# SCH_vdk.net
KiCad netlist of a schematic drawn in EasyEDA
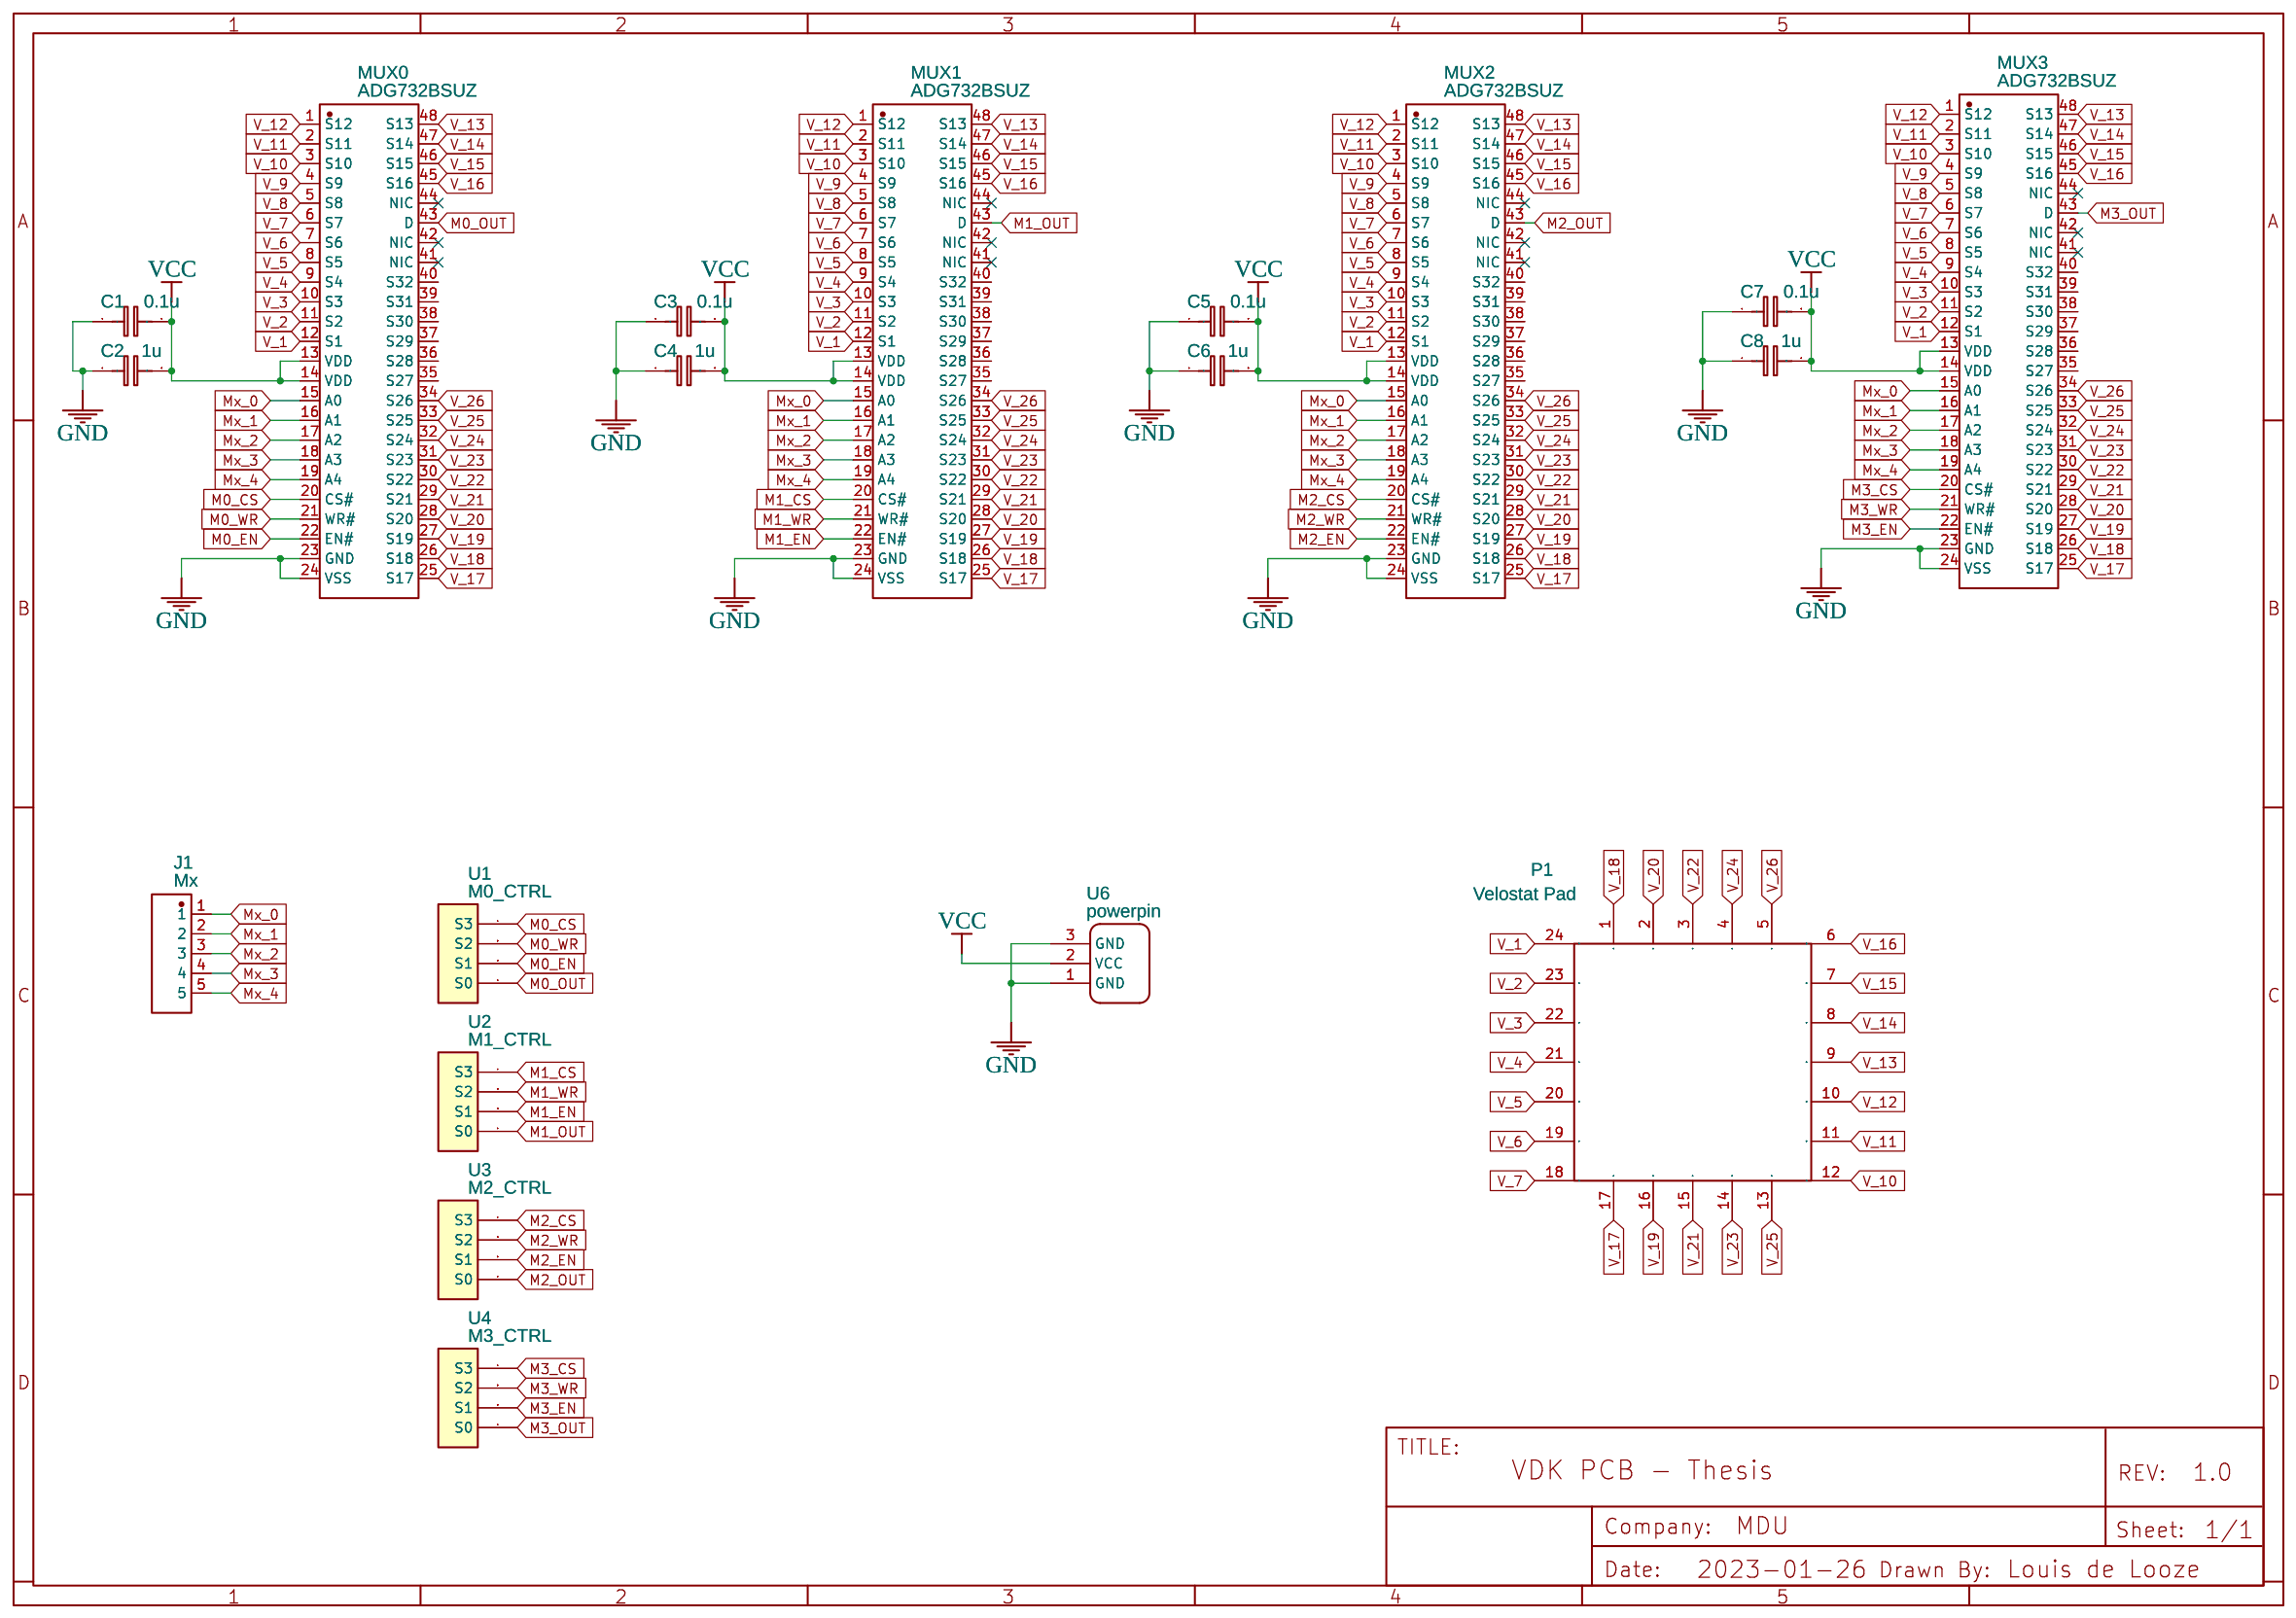
[diagram p0: schematic sheet]

(export (version "E")
  (design (tool "Eeschema 10.0.6"))
  (components
    (comp (ref "C1") (value "0.1u") (libsource (lib "") (part "Cap_0805_EU")))
    (comp (ref "C2") (value "1u") (libsource (lib "") (part "Cap_0805_EU")))
    (comp (ref "C3") (value "0.1u") (libsource (lib "") (part "Cap_0805_EU_1")))
    (comp (ref "C4") (value "1u") (libsource (lib "") (part "Cap_0805_EU_1")))
    (comp (ref "C5") (value "0.1u") (libsource (lib "") (part "Cap_0805_EU")))
    (comp (ref "C6") (value "1u") (libsource (lib "") (part "Cap_0805_EU")))
    (comp (ref "C7") (value "0.1u") (libsource (lib "") (part "Cap_0805_EU")))
    (comp (ref "C8") (value "1u") (libsource (lib "") (part "Cap_0805_EU")))
    (comp (ref "J1") (value "Mx") (libsource (lib "") (part "5-pin")))
    (comp (ref "MUX0")
      (value "ADG732BSUZ")
      (fields (field (name "BOM_Supplier Part") "C579103"))
      (libsource (lib "") (part "ADG732BSUZ"))
    )
    (comp (ref "MUX1")
      (value "ADG732BSUZ")
      (fields (field (name "BOM_Supplier Part") "C579103"))
      (libsource (lib "") (part "ADG732BSUZ"))
    )
    (comp (ref "MUX2")
      (value "ADG732BSUZ")
      (fields (field (name "BOM_Supplier Part") "C579103"))
      (libsource (lib "") (part "ADG732BSUZ"))
    )
    (comp (ref "MUX3")
      (value "ADG732BSUZ")
      (fields (field (name "BOM_Supplier Part") "C579103"))
      (libsource (lib "") (part "ADG732BSUZ"))
    )
    (comp (ref "P1") (value "Velostat Pad") (libsource (lib "") (part "Velostat Pad")))
    (comp (ref "U1")
      (value "M0_CTRL")
      (fields (field (name "BOM_Manufacturer Part") "New SchematicLib"))
      (libsource (lib "") (part "4 pin 16ch mux control"))
    )
    (comp (ref "U2")
      (value "M1_CTRL")
      (fields (field (name "BOM_Manufacturer Part") "New SchematicLib"))
      (libsource (lib "") (part "4 pin 16ch mux control"))
    )
    (comp (ref "U3")
      (value "M2_CTRL")
      (fields (field (name "BOM_Manufacturer Part") "New SchematicLib"))
      (libsource (lib "") (part "4 pin 16ch mux control"))
    )
    (comp (ref "U4")
      (value "M3_CTRL")
      (fields (field (name "BOM_Manufacturer Part") "New SchematicLib"))
      (libsource (lib "") (part "4 pin 16ch mux control"))
    )
    (comp (ref "U6") (value "powerpin") (libsource (lib "") (part "servo-header-3pin")))
  )
  (nets
    (net (code "1") (name "GND") (class "Default")
      (node (ref "C1") (pin "1") (pinfunction "1_1") (pintype "unspecified"))
      (node (ref "C2") (pin "1") (pinfunction "1_1") (pintype "unspecified"))
      (node (ref "C3") (pin "1") (pinfunction "1_1") (pintype "unspecified"))
      (node (ref "C4") (pin "1") (pinfunction "1_1") (pintype "unspecified"))
      (node (ref "C5") (pin "1") (pinfunction "1_1") (pintype "unspecified"))
      (node (ref "C6") (pin "1") (pinfunction "1_1") (pintype "unspecified"))
      (node (ref "C7") (pin "1") (pinfunction "1_1") (pintype "unspecified"))
      (node (ref "C8") (pin "1") (pinfunction "1_1") (pintype "unspecified"))
      (node (ref "MUX0") (pin "23") (pinfunction "GND_23") (pintype "unspecified"))
      (node (ref "MUX0") (pin "24") (pinfunction "VSS_24") (pintype "unspecified"))
      (node (ref "MUX1") (pin "23") (pinfunction "GND_23") (pintype "unspecified"))
      (node (ref "MUX1") (pin "24") (pinfunction "VSS_24") (pintype "unspecified"))
      (node (ref "MUX2") (pin "23") (pinfunction "GND_23") (pintype "unspecified"))
      (node (ref "MUX2") (pin "24") (pinfunction "VSS_24") (pintype "unspecified"))
      (node (ref "MUX3") (pin "23") (pinfunction "GND_23") (pintype "unspecified"))
      (node (ref "MUX3") (pin "24") (pinfunction "VSS_24") (pintype "unspecified"))
      (node (ref "U6") (pin "1") (pinfunction "GND_1") (pintype "unspecified"))
      (node (ref "U6") (pin "3") (pinfunction "GND_3") (pintype "unspecified"))
    )
    (net (code "2") (name "M0_CS") (class "Default")
      (node (ref "MUX0") (pin "20") (pinfunction "CS#_20") (pintype "unspecified"))
      (node (ref "U1") (pin "4") (pinfunction "S3_4") (pintype "input"))
    )
    (net (code "3") (name "M0_EN") (class "Default")
      (node (ref "MUX0") (pin "22") (pinfunction "EN#_22") (pintype "unspecified"))
      (node (ref "U1") (pin "2") (pinfunction "S1_2") (pintype "input"))
    )
    (net (code "4") (name "M0_OUT") (class "Default")
      (node (ref "MUX0") (pin "43") (pinfunction "D_43") (pintype "unspecified"))
      (node (ref "U1") (pin "1") (pinfunction "S0_1") (pintype "input"))
    )
    (net (code "5") (name "M0_WR") (class "Default")
      (node (ref "MUX0") (pin "21") (pinfunction "WR#_21") (pintype "unspecified"))
      (node (ref "U1") (pin "3") (pinfunction "S2_3") (pintype "input"))
    )
    (net (code "6") (name "M1_CS") (class "Default")
      (node (ref "MUX1") (pin "20") (pinfunction "CS#_20") (pintype "unspecified"))
      (node (ref "U2") (pin "4") (pinfunction "S3_4") (pintype "input"))
    )
    (net (code "7") (name "M1_EN") (class "Default")
      (node (ref "MUX1") (pin "22") (pinfunction "EN#_22") (pintype "unspecified"))
      (node (ref "U2") (pin "2") (pinfunction "S1_2") (pintype "input"))
    )
    (net (code "8") (name "M1_OUT") (class "Default")
      (node (ref "MUX1") (pin "43") (pinfunction "D_43") (pintype "unspecified"))
      (node (ref "U2") (pin "1") (pinfunction "S0_1") (pintype "input"))
    )
    (net (code "9") (name "M1_WR") (class "Default")
      (node (ref "MUX1") (pin "21") (pinfunction "WR#_21") (pintype "unspecified"))
      (node (ref "U2") (pin "3") (pinfunction "S2_3") (pintype "input"))
    )
    (net (code "10") (name "M2_CS") (class "Default")
      (node (ref "MUX2") (pin "20") (pinfunction "CS#_20") (pintype "unspecified"))
      (node (ref "U3") (pin "4") (pinfunction "S3_4") (pintype "input"))
    )
    (net (code "11") (name "M2_EN") (class "Default")
      (node (ref "MUX2") (pin "22") (pinfunction "EN#_22") (pintype "unspecified"))
      (node (ref "U3") (pin "2") (pinfunction "S1_2") (pintype "input"))
    )
    (net (code "12") (name "M2_OUT") (class "Default")
      (node (ref "MUX2") (pin "43") (pinfunction "D_43") (pintype "unspecified"))
      (node (ref "U3") (pin "1") (pinfunction "S0_1") (pintype "input"))
    )
    (net (code "13") (name "M2_WR") (class "Default")
      (node (ref "MUX2") (pin "21") (pinfunction "WR#_21") (pintype "unspecified"))
      (node (ref "U3") (pin "3") (pinfunction "S2_3") (pintype "input"))
    )
    (net (code "14") (name "M3_CS") (class "Default")
      (node (ref "MUX3") (pin "20") (pinfunction "CS#_20") (pintype "unspecified"))
      (node (ref "U4") (pin "4") (pinfunction "S3_4") (pintype "input"))
    )
    (net (code "15") (name "M3_EN") (class "Default")
      (node (ref "MUX3") (pin "22") (pinfunction "EN#_22") (pintype "unspecified"))
      (node (ref "U4") (pin "2") (pinfunction "S1_2") (pintype "input"))
    )
    (net (code "16") (name "M3_OUT") (class "Default")
      (node (ref "MUX3") (pin "43") (pinfunction "D_43") (pintype "unspecified"))
      (node (ref "U4") (pin "1") (pinfunction "S0_1") (pintype "input"))
    )
    (net (code "17") (name "M3_WR") (class "Default")
      (node (ref "MUX3") (pin "21") (pinfunction "WR#_21") (pintype "unspecified"))
      (node (ref "U4") (pin "3") (pinfunction "S2_3") (pintype "input"))
    )
    (net (code "18") (name "Mx_0") (class "Default")
      (node (ref "J1") (pin "1") (pinfunction "1_1") (pintype "unspecified"))
      (node (ref "MUX0") (pin "15") (pinfunction "A0_15") (pintype "unspecified"))
      (node (ref "MUX1") (pin "15") (pinfunction "A0_15") (pintype "unspecified"))
      (node (ref "MUX2") (pin "15") (pinfunction "A0_15") (pintype "unspecified"))
      (node (ref "MUX3") (pin "15") (pinfunction "A0_15") (pintype "unspecified"))
    )
    (net (code "19") (name "Mx_1") (class "Default")
      (node (ref "J1") (pin "2") (pinfunction "2_2") (pintype "unspecified"))
      (node (ref "MUX0") (pin "16") (pinfunction "A1_16") (pintype "unspecified"))
      (node (ref "MUX1") (pin "16") (pinfunction "A1_16") (pintype "unspecified"))
      (node (ref "MUX2") (pin "16") (pinfunction "A1_16") (pintype "unspecified"))
      (node (ref "MUX3") (pin "16") (pinfunction "A1_16") (pintype "unspecified"))
    )
    (net (code "20") (name "Mx_2") (class "Default")
      (node (ref "J1") (pin "3") (pinfunction "3_3") (pintype "unspecified"))
      (node (ref "MUX0") (pin "17") (pinfunction "A2_17") (pintype "unspecified"))
      (node (ref "MUX1") (pin "17") (pinfunction "A2_17") (pintype "unspecified"))
      (node (ref "MUX2") (pin "17") (pinfunction "A2_17") (pintype "unspecified"))
      (node (ref "MUX3") (pin "17") (pinfunction "A2_17") (pintype "unspecified"))
    )
    (net (code "21") (name "Mx_3") (class "Default")
      (node (ref "J1") (pin "4") (pinfunction "4_4") (pintype "unspecified"))
      (node (ref "MUX0") (pin "18") (pinfunction "A3_18") (pintype "unspecified"))
      (node (ref "MUX1") (pin "18") (pinfunction "A3_18") (pintype "unspecified"))
      (node (ref "MUX2") (pin "18") (pinfunction "A3_18") (pintype "unspecified"))
      (node (ref "MUX3") (pin "18") (pinfunction "A3_18") (pintype "unspecified"))
    )
    (net (code "22") (name "Mx_4") (class "Default")
      (node (ref "J1") (pin "5") (pinfunction "5_5") (pintype "unspecified"))
      (node (ref "MUX0") (pin "19") (pinfunction "A4_19") (pintype "unspecified"))
      (node (ref "MUX1") (pin "19") (pinfunction "A4_19") (pintype "unspecified"))
      (node (ref "MUX2") (pin "19") (pinfunction "A4_19") (pintype "unspecified"))
      (node (ref "MUX3") (pin "19") (pinfunction "A4_19") (pintype "unspecified"))
    )
    (net (code "23") (name "VCC") (class "Default")
      (node (ref "C1") (pin "2") (pinfunction "2_2") (pintype "unspecified"))
      (node (ref "C2") (pin "2") (pinfunction "2_2") (pintype "unspecified"))
      (node (ref "C3") (pin "2") (pinfunction "2_2") (pintype "unspecified"))
      (node (ref "C4") (pin "2") (pinfunction "2_2") (pintype "unspecified"))
      (node (ref "C5") (pin "2") (pinfunction "2_2") (pintype "unspecified"))
      (node (ref "C6") (pin "2") (pinfunction "2_2") (pintype "unspecified"))
      (node (ref "C7") (pin "2") (pinfunction "2_2") (pintype "unspecified"))
      (node (ref "C8") (pin "2") (pinfunction "2_2") (pintype "unspecified"))
      (node (ref "MUX0") (pin "13") (pinfunction "VDD_13") (pintype "unspecified"))
      (node (ref "MUX0") (pin "14") (pinfunction "VDD_14") (pintype "unspecified"))
      (node (ref "MUX1") (pin "13") (pinfunction "VDD_13") (pintype "unspecified"))
      (node (ref "MUX1") (pin "14") (pinfunction "VDD_14") (pintype "unspecified"))
      (node (ref "MUX2") (pin "13") (pinfunction "VDD_13") (pintype "unspecified"))
      (node (ref "MUX2") (pin "14") (pinfunction "VDD_14") (pintype "unspecified"))
      (node (ref "MUX3") (pin "13") (pinfunction "VDD_13") (pintype "unspecified"))
      (node (ref "MUX3") (pin "14") (pinfunction "VDD_14") (pintype "unspecified"))
      (node (ref "U6") (pin "2") (pinfunction "VCC_2") (pintype "unspecified"))
    )
    (net (code "24") (name "V_1") (class "Default")
      (node (ref "MUX0") (pin "12") (pinfunction "S1_12") (pintype "unspecified"))
      (node (ref "MUX1") (pin "12") (pinfunction "S1_12") (pintype "unspecified"))
      (node (ref "MUX2") (pin "12") (pinfunction "S1_12") (pintype "unspecified"))
      (node (ref "MUX3") (pin "12") (pinfunction "S1_12") (pintype "unspecified"))
      (node (ref "P1") (pin "24") (pinfunction "1_24") (pintype "unspecified"))
    )
    (net (code "25") (name "V_2") (class "Default")
      (node (ref "MUX0") (pin "11") (pinfunction "S2_11") (pintype "unspecified"))
      (node (ref "MUX1") (pin "11") (pinfunction "S2_11") (pintype "unspecified"))
      (node (ref "MUX2") (pin "11") (pinfunction "S2_11") (pintype "unspecified"))
      (node (ref "MUX3") (pin "11") (pinfunction "S2_11") (pintype "unspecified"))
      (node (ref "P1") (pin "23") (pinfunction "1_23") (pintype "unspecified"))
    )
    (net (code "26") (name "V_3") (class "Default")
      (node (ref "MUX0") (pin "10") (pinfunction "S3_10") (pintype "unspecified"))
      (node (ref "MUX1") (pin "10") (pinfunction "S3_10") (pintype "unspecified"))
      (node (ref "MUX2") (pin "10") (pinfunction "S3_10") (pintype "unspecified"))
      (node (ref "MUX3") (pin "10") (pinfunction "S3_10") (pintype "unspecified"))
      (node (ref "P1") (pin "22") (pinfunction "1_22") (pintype "unspecified"))
    )
    (net (code "27") (name "V_4") (class "Default")
      (node (ref "MUX0") (pin "9") (pinfunction "S4_9") (pintype "unspecified"))
      (node (ref "MUX1") (pin "9") (pinfunction "S4_9") (pintype "unspecified"))
      (node (ref "MUX2") (pin "9") (pinfunction "S4_9") (pintype "unspecified"))
      (node (ref "MUX3") (pin "9") (pinfunction "S4_9") (pintype "unspecified"))
      (node (ref "P1") (pin "21") (pinfunction "1_21") (pintype "unspecified"))
    )
    (net (code "28") (name "V_5") (class "Default")
      (node (ref "MUX0") (pin "8") (pinfunction "S5_8") (pintype "unspecified"))
      (node (ref "MUX1") (pin "8") (pinfunction "S5_8") (pintype "unspecified"))
      (node (ref "MUX2") (pin "8") (pinfunction "S5_8") (pintype "unspecified"))
      (node (ref "MUX3") (pin "8") (pinfunction "S5_8") (pintype "unspecified"))
      (node (ref "P1") (pin "20") (pinfunction "1_20") (pintype "unspecified"))
    )
    (net (code "29") (name "V_6") (class "Default")
      (node (ref "MUX0") (pin "7") (pinfunction "S6_7") (pintype "unspecified"))
      (node (ref "MUX1") (pin "7") (pinfunction "S6_7") (pintype "unspecified"))
      (node (ref "MUX2") (pin "7") (pinfunction "S6_7") (pintype "unspecified"))
      (node (ref "MUX3") (pin "7") (pinfunction "S6_7") (pintype "unspecified"))
      (node (ref "P1") (pin "19") (pinfunction "1_19") (pintype "unspecified"))
    )
    (net (code "30") (name "V_7") (class "Default")
      (node (ref "MUX0") (pin "6") (pinfunction "S7_6") (pintype "unspecified"))
      (node (ref "MUX1") (pin "6") (pinfunction "S7_6") (pintype "unspecified"))
      (node (ref "MUX2") (pin "6") (pinfunction "S7_6") (pintype "unspecified"))
      (node (ref "MUX3") (pin "6") (pinfunction "S7_6") (pintype "unspecified"))
      (node (ref "P1") (pin "18") (pinfunction "1_18") (pintype "unspecified"))
    )
    (net (code "31") (name "V_8") (class "Default")
      (node (ref "MUX0") (pin "5") (pinfunction "S8_5") (pintype "unspecified"))
      (node (ref "MUX1") (pin "5") (pinfunction "S8_5") (pintype "unspecified"))
      (node (ref "MUX2") (pin "5") (pinfunction "S8_5") (pintype "unspecified"))
      (node (ref "MUX3") (pin "5") (pinfunction "S8_5") (pintype "unspecified"))
    )
    (net (code "32") (name "V_9") (class "Default")
      (node (ref "MUX0") (pin "4") (pinfunction "S9_4") (pintype "unspecified"))
      (node (ref "MUX1") (pin "4") (pinfunction "S9_4") (pintype "unspecified"))
      (node (ref "MUX2") (pin "4") (pinfunction "S9_4") (pintype "unspecified"))
      (node (ref "MUX3") (pin "4") (pinfunction "S9_4") (pintype "unspecified"))
    )
    (net (code "33") (name "V_10") (class "Default")
      (node (ref "MUX0") (pin "3") (pinfunction "S10_3") (pintype "unspecified"))
      (node (ref "MUX1") (pin "3") (pinfunction "S10_3") (pintype "unspecified"))
      (node (ref "MUX2") (pin "3") (pinfunction "S10_3") (pintype "unspecified"))
      (node (ref "MUX3") (pin "3") (pinfunction "S10_3") (pintype "unspecified"))
      (node (ref "P1") (pin "12") (pinfunction "2_12") (pintype "unspecified"))
    )
    (net (code "34") (name "V_11") (class "Default")
      (node (ref "MUX0") (pin "2") (pinfunction "S11_2") (pintype "unspecified"))
      (node (ref "MUX1") (pin "2") (pinfunction "S11_2") (pintype "unspecified"))
      (node (ref "MUX2") (pin "2") (pinfunction "S11_2") (pintype "unspecified"))
      (node (ref "MUX3") (pin "2") (pinfunction "S11_2") (pintype "unspecified"))
      (node (ref "P1") (pin "11") (pinfunction "2_11") (pintype "unspecified"))
    )
    (net (code "35") (name "V_12") (class "Default")
      (node (ref "MUX0") (pin "1") (pinfunction "S12_1") (pintype "unspecified"))
      (node (ref "MUX1") (pin "1") (pinfunction "S12_1") (pintype "unspecified"))
      (node (ref "MUX2") (pin "1") (pinfunction "S12_1") (pintype "unspecified"))
      (node (ref "MUX3") (pin "1") (pinfunction "S12_1") (pintype "unspecified"))
      (node (ref "P1") (pin "10") (pinfunction "2_10") (pintype "unspecified"))
    )
    (net (code "36") (name "V_13") (class "Default")
      (node (ref "MUX0") (pin "48") (pinfunction "S13_48") (pintype "unspecified"))
      (node (ref "MUX1") (pin "48") (pinfunction "S13_48") (pintype "unspecified"))
      (node (ref "MUX2") (pin "48") (pinfunction "S13_48") (pintype "unspecified"))
      (node (ref "MUX3") (pin "48") (pinfunction "S13_48") (pintype "unspecified"))
      (node (ref "P1") (pin "9") (pinfunction "2_9") (pintype "unspecified"))
    )
    (net (code "37") (name "V_14") (class "Default")
      (node (ref "MUX0") (pin "47") (pinfunction "S14_47") (pintype "unspecified"))
      (node (ref "MUX1") (pin "47") (pinfunction "S14_47") (pintype "unspecified"))
      (node (ref "MUX2") (pin "47") (pinfunction "S14_47") (pintype "unspecified"))
      (node (ref "MUX3") (pin "47") (pinfunction "S14_47") (pintype "unspecified"))
      (node (ref "P1") (pin "8") (pinfunction "2_8") (pintype "unspecified"))
    )
    (net (code "38") (name "V_15") (class "Default")
      (node (ref "MUX0") (pin "46") (pinfunction "S15_46") (pintype "unspecified"))
      (node (ref "MUX1") (pin "46") (pinfunction "S15_46") (pintype "unspecified"))
      (node (ref "MUX2") (pin "46") (pinfunction "S15_46") (pintype "unspecified"))
      (node (ref "MUX3") (pin "46") (pinfunction "S15_46") (pintype "unspecified"))
      (node (ref "P1") (pin "7") (pinfunction "2_7") (pintype "unspecified"))
    )
    (net (code "39") (name "V_16") (class "Default")
      (node (ref "MUX0") (pin "45") (pinfunction "S16_45") (pintype "unspecified"))
      (node (ref "MUX1") (pin "45") (pinfunction "S16_45") (pintype "unspecified"))
      (node (ref "MUX2") (pin "45") (pinfunction "S16_45") (pintype "unspecified"))
      (node (ref "MUX3") (pin "45") (pinfunction "S16_45") (pintype "unspecified"))
      (node (ref "P1") (pin "6") (pinfunction "2_6") (pintype "unspecified"))
    )
    (net (code "40") (name "V_17") (class "Default")
      (node (ref "MUX0") (pin "25") (pinfunction "S17_25") (pintype "unspecified"))
      (node (ref "MUX1") (pin "25") (pinfunction "S17_25") (pintype "unspecified"))
      (node (ref "MUX2") (pin "25") (pinfunction "S17_25") (pintype "unspecified"))
      (node (ref "MUX3") (pin "25") (pinfunction "S17_25") (pintype "unspecified"))
      (node (ref "P1") (pin "17") (pinfunction "1_17") (pintype "unspecified"))
    )
    (net (code "41") (name "V_18") (class "Default")
      (node (ref "MUX0") (pin "26") (pinfunction "S18_26") (pintype "unspecified"))
      (node (ref "MUX1") (pin "26") (pinfunction "S18_26") (pintype "unspecified"))
      (node (ref "MUX2") (pin "26") (pinfunction "S18_26") (pintype "unspecified"))
      (node (ref "MUX3") (pin "26") (pinfunction "S18_26") (pintype "unspecified"))
      (node (ref "P1") (pin "1") (pinfunction "1_1") (pintype "unspecified"))
    )
    (net (code "42") (name "V_19") (class "Default")
      (node (ref "MUX0") (pin "27") (pinfunction "S19_27") (pintype "unspecified"))
      (node (ref "MUX1") (pin "27") (pinfunction "S19_27") (pintype "unspecified"))
      (node (ref "MUX2") (pin "27") (pinfunction "S19_27") (pintype "unspecified"))
      (node (ref "MUX3") (pin "27") (pinfunction "S19_27") (pintype "unspecified"))
      (node (ref "P1") (pin "16") (pinfunction "1_16") (pintype "unspecified"))
    )
    (net (code "43") (name "V_20") (class "Default")
      (node (ref "MUX0") (pin "28") (pinfunction "S20_28") (pintype "unspecified"))
      (node (ref "MUX1") (pin "28") (pinfunction "S20_28") (pintype "unspecified"))
      (node (ref "MUX2") (pin "28") (pinfunction "S20_28") (pintype "unspecified"))
      (node (ref "MUX3") (pin "28") (pinfunction "S20_28") (pintype "unspecified"))
      (node (ref "P1") (pin "2") (pinfunction "1_2") (pintype "unspecified"))
    )
    (net (code "44") (name "V_21") (class "Default")
      (node (ref "MUX0") (pin "29") (pinfunction "S21_29") (pintype "unspecified"))
      (node (ref "MUX1") (pin "29") (pinfunction "S21_29") (pintype "unspecified"))
      (node (ref "MUX2") (pin "29") (pinfunction "S21_29") (pintype "unspecified"))
      (node (ref "MUX3") (pin "29") (pinfunction "S21_29") (pintype "unspecified"))
      (node (ref "P1") (pin "15") (pinfunction "1_15") (pintype "unspecified"))
    )
    (net (code "45") (name "V_22") (class "Default")
      (node (ref "MUX0") (pin "30") (pinfunction "S22_30") (pintype "unspecified"))
      (node (ref "MUX1") (pin "30") (pinfunction "S22_30") (pintype "unspecified"))
      (node (ref "MUX2") (pin "30") (pinfunction "S22_30") (pintype "unspecified"))
      (node (ref "MUX3") (pin "30") (pinfunction "S22_30") (pintype "unspecified"))
      (node (ref "P1") (pin "3") (pinfunction "1_3") (pintype "unspecified"))
    )
    (net (code "46") (name "V_23") (class "Default")
      (node (ref "MUX0") (pin "31") (pinfunction "S23_31") (pintype "unspecified"))
      (node (ref "MUX1") (pin "31") (pinfunction "S23_31") (pintype "unspecified"))
      (node (ref "MUX2") (pin "31") (pinfunction "S23_31") (pintype "unspecified"))
      (node (ref "MUX3") (pin "31") (pinfunction "S23_31") (pintype "unspecified"))
      (node (ref "P1") (pin "14") (pinfunction "1_14") (pintype "unspecified"))
    )
    (net (code "47") (name "V_24") (class "Default")
      (node (ref "MUX0") (pin "32") (pinfunction "S24_32") (pintype "unspecified"))
      (node (ref "MUX1") (pin "32") (pinfunction "S24_32") (pintype "unspecified"))
      (node (ref "MUX2") (pin "32") (pinfunction "S24_32") (pintype "unspecified"))
      (node (ref "MUX3") (pin "32") (pinfunction "S24_32") (pintype "unspecified"))
      (node (ref "P1") (pin "4") (pinfunction "1_4") (pintype "unspecified"))
    )
    (net (code "48") (name "V_25") (class "Default")
      (node (ref "MUX0") (pin "33") (pinfunction "S25_33") (pintype "unspecified"))
      (node (ref "MUX1") (pin "33") (pinfunction "S25_33") (pintype "unspecified"))
      (node (ref "MUX2") (pin "33") (pinfunction "S25_33") (pintype "unspecified"))
      (node (ref "MUX3") (pin "33") (pinfunction "S25_33") (pintype "unspecified"))
      (node (ref "P1") (pin "13") (pinfunction "1_13") (pintype "unspecified"))
    )
    (net (code "49") (name "V_26") (class "Default")
      (node (ref "MUX0") (pin "34") (pinfunction "S26_34") (pintype "unspecified"))
      (node (ref "MUX1") (pin "34") (pinfunction "S26_34") (pintype "unspecified"))
      (node (ref "MUX2") (pin "34") (pinfunction "S26_34") (pintype "unspecified"))
      (node (ref "MUX3") (pin "34") (pinfunction "S26_34") (pintype "unspecified"))
      (node (ref "P1") (pin "5") (pinfunction "1_5") (pintype "unspecified"))
    )
    (net (code "50") (name "unconnected-(MUX0-NIC-Pad41)") (class "Default")
      (node (ref "MUX0") (pin "41") (pinfunction "NIC_41") (pintype "unspecified+no_connect"))
    )
    (net (code "51") (name "unconnected-(MUX0-NIC-Pad42)") (class "Default")
      (node (ref "MUX0") (pin "42") (pinfunction "NIC_42") (pintype "unspecified+no_connect"))
    )
    (net (code "52") (name "unconnected-(MUX0-NIC-Pad44)") (class "Default")
      (node (ref "MUX0") (pin "44") (pinfunction "NIC_44") (pintype "unspecified+no_connect"))
    )
    (net (code "53") (name "unconnected-(MUX0-S27-Pad35)") (class "Default")
      (node (ref "MUX0") (pin "35") (pinfunction "S27_35") (pintype "unspecified"))
    )
    (net (code "54") (name "unconnected-(MUX0-S28-Pad36)") (class "Default")
      (node (ref "MUX0") (pin "36") (pinfunction "S28_36") (pintype "unspecified"))
    )
    (net (code "55") (name "unconnected-(MUX0-S29-Pad37)") (class "Default")
      (node (ref "MUX0") (pin "37") (pinfunction "S29_37") (pintype "unspecified"))
    )
    (net (code "56") (name "unconnected-(MUX0-S30-Pad38)") (class "Default")
      (node (ref "MUX0") (pin "38") (pinfunction "S30_38") (pintype "unspecified"))
    )
    (net (code "57") (name "unconnected-(MUX0-S31-Pad39)") (class "Default")
      (node (ref "MUX0") (pin "39") (pinfunction "S31_39") (pintype "unspecified"))
    )
    (net (code "58") (name "unconnected-(MUX0-S32-Pad40)") (class "Default")
      (node (ref "MUX0") (pin "40") (pinfunction "S32_40") (pintype "unspecified"))
    )
    (net (code "59") (name "unconnected-(MUX1-NIC-Pad41)") (class "Default")
      (node (ref "MUX1") (pin "41") (pinfunction "NIC_41") (pintype "unspecified+no_connect"))
    )
    (net (code "60") (name "unconnected-(MUX1-NIC-Pad42)") (class "Default")
      (node (ref "MUX1") (pin "42") (pinfunction "NIC_42") (pintype "unspecified+no_connect"))
    )
    (net (code "61") (name "unconnected-(MUX1-NIC-Pad44)") (class "Default")
      (node (ref "MUX1") (pin "44") (pinfunction "NIC_44") (pintype "unspecified+no_connect"))
    )
    (net (code "62") (name "unconnected-(MUX1-S27-Pad35)") (class "Default")
      (node (ref "MUX1") (pin "35") (pinfunction "S27_35") (pintype "unspecified"))
    )
    (net (code "63") (name "unconnected-(MUX1-S28-Pad36)") (class "Default")
      (node (ref "MUX1") (pin "36") (pinfunction "S28_36") (pintype "unspecified"))
    )
    (net (code "64") (name "unconnected-(MUX1-S29-Pad37)") (class "Default")
      (node (ref "MUX1") (pin "37") (pinfunction "S29_37") (pintype "unspecified"))
    )
    (net (code "65") (name "unconnected-(MUX1-S30-Pad38)") (class "Default")
      (node (ref "MUX1") (pin "38") (pinfunction "S30_38") (pintype "unspecified"))
    )
    (net (code "66") (name "unconnected-(MUX1-S31-Pad39)") (class "Default")
      (node (ref "MUX1") (pin "39") (pinfunction "S31_39") (pintype "unspecified"))
    )
    (net (code "67") (name "unconnected-(MUX1-S32-Pad40)") (class "Default")
      (node (ref "MUX1") (pin "40") (pinfunction "S32_40") (pintype "unspecified"))
    )
    (net (code "68") (name "unconnected-(MUX2-NIC-Pad41)") (class "Default")
      (node (ref "MUX2") (pin "41") (pinfunction "NIC_41") (pintype "unspecified+no_connect"))
    )
    (net (code "69") (name "unconnected-(MUX2-NIC-Pad42)") (class "Default")
      (node (ref "MUX2") (pin "42") (pinfunction "NIC_42") (pintype "unspecified+no_connect"))
    )
    (net (code "70") (name "unconnected-(MUX2-NIC-Pad44)") (class "Default")
      (node (ref "MUX2") (pin "44") (pinfunction "NIC_44") (pintype "unspecified+no_connect"))
    )
    (net (code "71") (name "unconnected-(MUX2-S27-Pad35)") (class "Default")
      (node (ref "MUX2") (pin "35") (pinfunction "S27_35") (pintype "unspecified"))
    )
    (net (code "72") (name "unconnected-(MUX2-S28-Pad36)") (class "Default")
      (node (ref "MUX2") (pin "36") (pinfunction "S28_36") (pintype "unspecified"))
    )
    (net (code "73") (name "unconnected-(MUX2-S29-Pad37)") (class "Default")
      (node (ref "MUX2") (pin "37") (pinfunction "S29_37") (pintype "unspecified"))
    )
    (net (code "74") (name "unconnected-(MUX2-S30-Pad38)") (class "Default")
      (node (ref "MUX2") (pin "38") (pinfunction "S30_38") (pintype "unspecified"))
    )
    (net (code "75") (name "unconnected-(MUX2-S31-Pad39)") (class "Default")
      (node (ref "MUX2") (pin "39") (pinfunction "S31_39") (pintype "unspecified"))
    )
    (net (code "76") (name "unconnected-(MUX2-S32-Pad40)") (class "Default")
      (node (ref "MUX2") (pin "40") (pinfunction "S32_40") (pintype "unspecified"))
    )
    (net (code "77") (name "unconnected-(MUX3-NIC-Pad41)") (class "Default")
      (node (ref "MUX3") (pin "41") (pinfunction "NIC_41") (pintype "unspecified+no_connect"))
    )
    (net (code "78") (name "unconnected-(MUX3-NIC-Pad42)") (class "Default")
      (node (ref "MUX3") (pin "42") (pinfunction "NIC_42") (pintype "unspecified+no_connect"))
    )
    (net (code "79") (name "unconnected-(MUX3-NIC-Pad44)") (class "Default")
      (node (ref "MUX3") (pin "44") (pinfunction "NIC_44") (pintype "unspecified+no_connect"))
    )
    (net (code "80") (name "unconnected-(MUX3-S27-Pad35)") (class "Default")
      (node (ref "MUX3") (pin "35") (pinfunction "S27_35") (pintype "unspecified"))
    )
    (net (code "81") (name "unconnected-(MUX3-S28-Pad36)") (class "Default")
      (node (ref "MUX3") (pin "36") (pinfunction "S28_36") (pintype "unspecified"))
    )
    (net (code "82") (name "unconnected-(MUX3-S29-Pad37)") (class "Default")
      (node (ref "MUX3") (pin "37") (pinfunction "S29_37") (pintype "unspecified"))
    )
    (net (code "83") (name "unconnected-(MUX3-S30-Pad38)") (class "Default")
      (node (ref "MUX3") (pin "38") (pinfunction "S30_38") (pintype "unspecified"))
    )
    (net (code "84") (name "unconnected-(MUX3-S31-Pad39)") (class "Default")
      (node (ref "MUX3") (pin "39") (pinfunction "S31_39") (pintype "unspecified"))
    )
    (net (code "85") (name "unconnected-(MUX3-S32-Pad40)") (class "Default")
      (node (ref "MUX3") (pin "40") (pinfunction "S32_40") (pintype "unspecified"))
    )
  )
)
